# TDS_EZO_2.net
KiCad netlist of a schematic drawn in Altium Designer
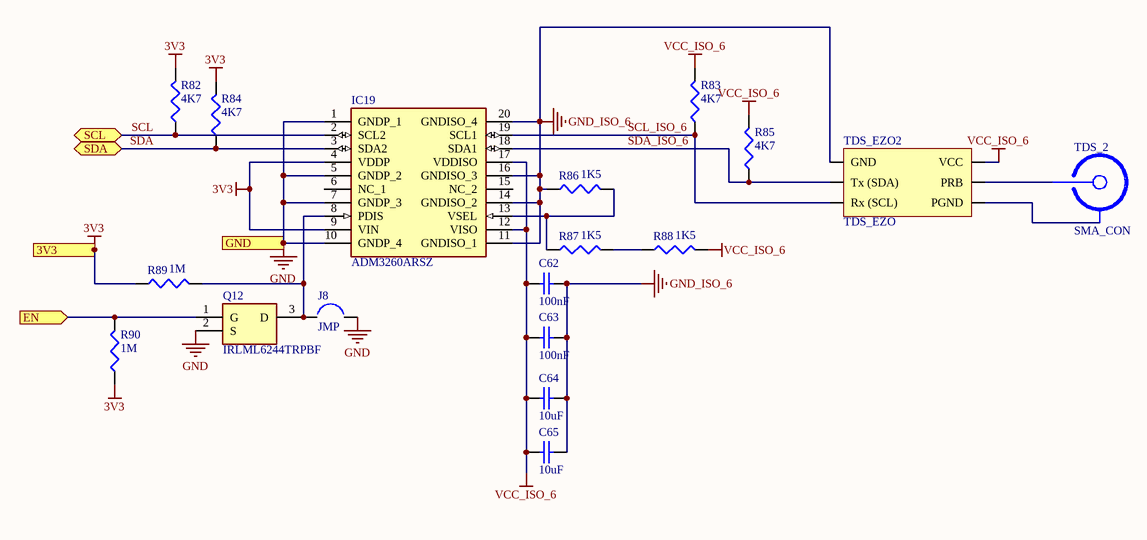
[diagram p0: TDS_EZO_2.SchDoc]

(export (version "E")
  (design (tool "Eeschema 10.0.6"))
  (components
    (comp (ref "C62")
      (value "100nF")
      (footprint "1608[0603]")
      (description "Capacitor (Semiconductor SIM Model)")
      (fields (field (name "PUBLISHER") "Altium Limited"))
      (libsource (lib "Miscellaneous Devices") (part "Cap Semi"))
    )
    (comp (ref "C63")
      (value "100nF")
      (footprint "1608[0603]")
      (description "Capacitor (Semiconductor SIM Model)")
      (fields (field (name "PUBLISHER") "Altium Limited"))
      (libsource (lib "Miscellaneous Devices") (part "Cap Semi"))
    )
    (comp (ref "C64")
      (value "10uF")
      (footprint "1608[0603]")
      (description "Capacitor (Semiconductor SIM Model)")
      (fields (field (name "PUBLISHER") "Altium Limited"))
      (libsource (lib "Miscellaneous Devices") (part "Cap Semi"))
    )
    (comp (ref "C65")
      (value "10uF")
      (footprint "1608[0603]")
      (description "Capacitor (Semiconductor SIM Model)")
      (fields (field (name "PUBLISHER") "Altium Limited"))
      (libsource (lib "Miscellaneous Devices") (part "Cap Semi"))
    )
    (comp (ref "IC19")
      (value "ADM3260ARSZ")
      (footprint "SOP65P780X200-20N")
      (description "Integrated Circuit")
      (fields
        (field (name "MOUSER PART NUMBER") "584-ADM3260ARSZ")
        (field (name "RS PART NUMBER") "8319113P")
      )
      (libsource (lib "SamacSys") (part "ADM3260ARSZ"))
    )
    (comp (ref "J8") (value "JMP") (footprint "Jumper") (libsource (lib "SamacSys") (part "JMP")))
    (comp (ref "Q12")
      (value "IRLML6244TRPBF")
      (footprint "SOT95P237X112-3N")
      (description "Transistor")
      (fields
        (field (name "MOUSER PART NUMBER") "942-IRLML6244TRPBF")
        (field (name "RS PART NUMBER") "7377228P")
      )
      (libsource (lib "SamacSys") (part "IRLML6244TRPBF"))
    )
    (comp (ref "R82")
      (value "4K7")
      (footprint "J1-0603")
      (description "Resistor")
      (fields (field (name "PUBLISHER") "Altium Limited"))
      (libsource (lib "Miscellaneous Devices") (part "Res3"))
    )
    (comp (ref "R83")
      (value "4K7")
      (footprint "J1-0603")
      (description "Resistor")
      (fields (field (name "PUBLISHER") "Altium Limited"))
      (libsource (lib "Miscellaneous Devices") (part "Res3"))
    )
    (comp (ref "R84")
      (value "4K7")
      (footprint "J1-0603")
      (description "Resistor")
      (fields (field (name "PUBLISHER") "Altium Limited"))
      (libsource (lib "Miscellaneous Devices") (part "Res3"))
    )
    (comp (ref "R85")
      (value "4K7")
      (footprint "J1-0603")
      (description "Resistor")
      (fields (field (name "PUBLISHER") "Altium Limited"))
      (libsource (lib "Miscellaneous Devices") (part "Res3"))
    )
    (comp (ref "R86")
      (value "1K5")
      (footprint "J1-0603")
      (description "Resistor")
      (fields (field (name "PUBLISHER") "Altium Limited"))
      (libsource (lib "Miscellaneous Devices") (part "Res3"))
    )
    (comp (ref "R87")
      (value "1K5")
      (footprint "J1-0603")
      (description "Resistor")
      (fields (field (name "PUBLISHER") "Altium Limited"))
      (libsource (lib "Miscellaneous Devices") (part "Res3"))
    )
    (comp (ref "R88")
      (value "1K5")
      (footprint "J1-0603")
      (description "Resistor")
      (fields (field (name "PUBLISHER") "Altium Limited"))
      (libsource (lib "Miscellaneous Devices") (part "Res3"))
    )
    (comp (ref "R89")
      (value "1M")
      (footprint "J1-0603")
      (description "Resistor")
      (fields (field (name "PUBLISHER") "Altium Limited"))
      (libsource (lib "Miscellaneous Devices") (part "Res3"))
    )
    (comp (ref "R90")
      (value "1M")
      (footprint "J1-0603")
      (description "Resistor")
      (fields (field (name "PUBLISHER") "Altium Limited"))
      (libsource (lib "Miscellaneous Devices") (part "Res3"))
    )
    (comp (ref "TDS_2")
      (value "SMA_CON")
      (footprint "SamacSys:PCBSMAFRAHT")
      (description "Connector")
      (fields
        (field (name "MANUFACTURER_PART_NUMBER") "PCB.SMAFRA.HT")
        (field (name "MOUSER PART NUMBER") "960-PCB.SMAFRA.HT")
      )
      (libsource (lib "SamacSys") (part "SMA"))
    )
    (comp (ref "TDS_EZO2")
      (value "TDS_EZO")
      (footprint "TDS_EZO")
      (libsource (lib "SamacSys") (part "TDS_EZO"))
    )
  )
  (nets
    (net (code "1") (name "/EN") (class "Default")
      (node (ref "Q12") (pin "1") (pinfunction "G_1") (pintype "passive"))
      (node (ref "R90") (pin "2") (pinfunction "2_2") (pintype "passive"))
    )
    (net (code "2") (name "/SCL") (class "Default")
      (node (ref "IC19") (pin "2") (pinfunction "SCL2_2") (pintype "bidirectional"))
      (node (ref "R82") (pin "1") (pinfunction "1_1") (pintype "passive"))
    )
    (net (code "3") (name "/SCL_ISO_6") (class "Default")
      (node (ref "IC19") (pin "19") (pinfunction "SCL1_19") (pintype "bidirectional"))
      (node (ref "R83") (pin "1") (pinfunction "1_1") (pintype "passive"))
      (node (ref "TDS_EZO2") (pin "3") (pinfunction "Rx_(SCL)_3") (pintype "passive"))
    )
    (net (code "4") (name "/SDA") (class "Default")
      (node (ref "IC19") (pin "3") (pinfunction "SDA2_3") (pintype "bidirectional"))
      (node (ref "R84") (pin "1") (pinfunction "1_1") (pintype "passive"))
    )
    (net (code "5") (name "/SDA_ISO_6") (class "Default")
      (node (ref "IC19") (pin "18") (pinfunction "SDA1_18") (pintype "bidirectional"))
      (node (ref "R85") (pin "1") (pinfunction "1_1") (pintype "passive"))
      (node (ref "TDS_EZO2") (pin "2") (pinfunction "Tx_(SDA)_2") (pintype "passive"))
    )
    (net (code "6") (name "3V3") (class "Default")
      (node (ref "IC19") (pin "4") (pinfunction "VDDP_4") (pintype "power_in"))
      (node (ref "IC19") (pin "9") (pinfunction "VIN_9") (pintype "power_in"))
      (node (ref "R82") (pin "2") (pinfunction "2_2") (pintype "passive"))
      (node (ref "R84") (pin "2") (pinfunction "2_2") (pintype "passive"))
      (node (ref "R89") (pin "1") (pinfunction "1_1") (pintype "passive"))
      (node (ref "R90") (pin "1") (pinfunction "1_1") (pintype "passive"))
    )
    (net (code "7") (name "GND") (class "Default")
      (node (ref "IC19") (pin "1") (pinfunction "GNDP_1_1") (pintype "power_in"))
      (node (ref "IC19") (pin "10") (pinfunction "GNDP_4_10") (pintype "power_in"))
      (node (ref "IC19") (pin "5") (pinfunction "GNDP_2_5") (pintype "power_in"))
      (node (ref "IC19") (pin "7") (pinfunction "GNDP_3_7") (pintype "power_in"))
      (node (ref "J8") (pin "2") (pinfunction "2_2") (pintype "passive"))
      (node (ref "Q12") (pin "2") (pinfunction "S_2") (pintype "passive"))
    )
    (net (code "8") (name "GND_ISO_6") (class "Default")
      (node (ref "C62") (pin "2") (pinfunction "2_2") (pintype "passive"))
      (node (ref "C63") (pin "2") (pinfunction "2_2") (pintype "passive"))
      (node (ref "C64") (pin "2") (pinfunction "2_2") (pintype "passive"))
      (node (ref "C65") (pin "2") (pinfunction "2_2") (pintype "passive"))
      (node (ref "IC19") (pin "11") (pinfunction "GNDISO_1_11") (pintype "power_in"))
      (node (ref "IC19") (pin "14") (pinfunction "GNDISO_2_14") (pintype "power_in"))
      (node (ref "IC19") (pin "16") (pinfunction "GNDISO_3_16") (pintype "power_in"))
      (node (ref "IC19") (pin "20") (pinfunction "GNDISO_4_20") (pintype "power_in"))
      (node (ref "R86") (pin "1") (pinfunction "1_1") (pintype "passive"))
      (node (ref "TDS_EZO2") (pin "1") (pinfunction "GND_1") (pintype "passive"))
    )
    (net (code "9") (name "Net-(IC19-PDIS)") (class "Default")
      (node (ref "IC19") (pin "8") (pinfunction "PDIS_8") (pintype "input"))
      (node (ref "J8") (pin "1") (pinfunction "1_1") (pintype "passive"))
      (node (ref "Q12") (pin "3") (pinfunction "D_3") (pintype "passive"))
      (node (ref "R89") (pin "2") (pinfunction "2_2") (pintype "passive"))
    )
    (net (code "10") (name "Net-(IC19-VSEL)") (class "Default")
      (node (ref "IC19") (pin "13") (pinfunction "VSEL_13") (pintype "input"))
      (node (ref "R86") (pin "2") (pinfunction "2_2") (pintype "passive"))
      (node (ref "R87") (pin "1") (pinfunction "1_1") (pintype "passive"))
    )
    (net (code "11") (name "Net-(R87-Pad2)") (class "Default")
      (node (ref "R87") (pin "2") (pinfunction "2_2") (pintype "passive"))
      (node (ref "R88") (pin "1") (pinfunction "1_1") (pintype "passive"))
    )
    (net (code "12") (name "Net-(TDS_EZO2-PGND)") (class "Default")
      (node (ref "TDS_2") (pin "2") (pintype "passive"))
      (node (ref "TDS_EZO2") (pin "6") (pinfunction "PGND_6") (pintype "passive"))
    )
    (net (code "13") (name "Net-(TDS_EZO2-PRB)") (class "Default")
      (node (ref "TDS_2") (pin "1") (pintype "passive"))
      (node (ref "TDS_EZO2") (pin "5") (pinfunction "PRB_5") (pintype "passive"))
    )
    (net (code "14") (name "VCC_ISO_6") (class "Default")
      (node (ref "C62") (pin "1") (pinfunction "1_1") (pintype "passive"))
      (node (ref "C63") (pin "1") (pinfunction "1_1") (pintype "passive"))
      (node (ref "C64") (pin "1") (pinfunction "1_1") (pintype "passive"))
      (node (ref "C65") (pin "1") (pinfunction "1_1") (pintype "passive"))
      (node (ref "IC19") (pin "12") (pinfunction "VISO_12") (pintype "power_in"))
      (node (ref "IC19") (pin "17") (pinfunction "VDDISO_17") (pintype "power_in"))
      (node (ref "R83") (pin "2") (pinfunction "2_2") (pintype "passive"))
      (node (ref "R85") (pin "2") (pinfunction "2_2") (pintype "passive"))
      (node (ref "R88") (pin "2") (pinfunction "2_2") (pintype "passive"))
      (node (ref "TDS_EZO2") (pin "4") (pinfunction "VCC_4") (pintype "passive"))
    )
    (net (code "15") (name "unconnected-(IC19-NC_1-Pad6)") (class "Default")
      (node (ref "IC19") (pin "6") (pinfunction "NC_1_6") (pintype "passive"))
    )
    (net (code "16") (name "unconnected-(IC19-NC_2-Pad15)") (class "Default")
      (node (ref "IC19") (pin "15") (pinfunction "NC_2_15") (pintype "passive"))
    )
  )
)
